# wctrl_led.net
KiCad netlist of a schematic drawn in EAGLE
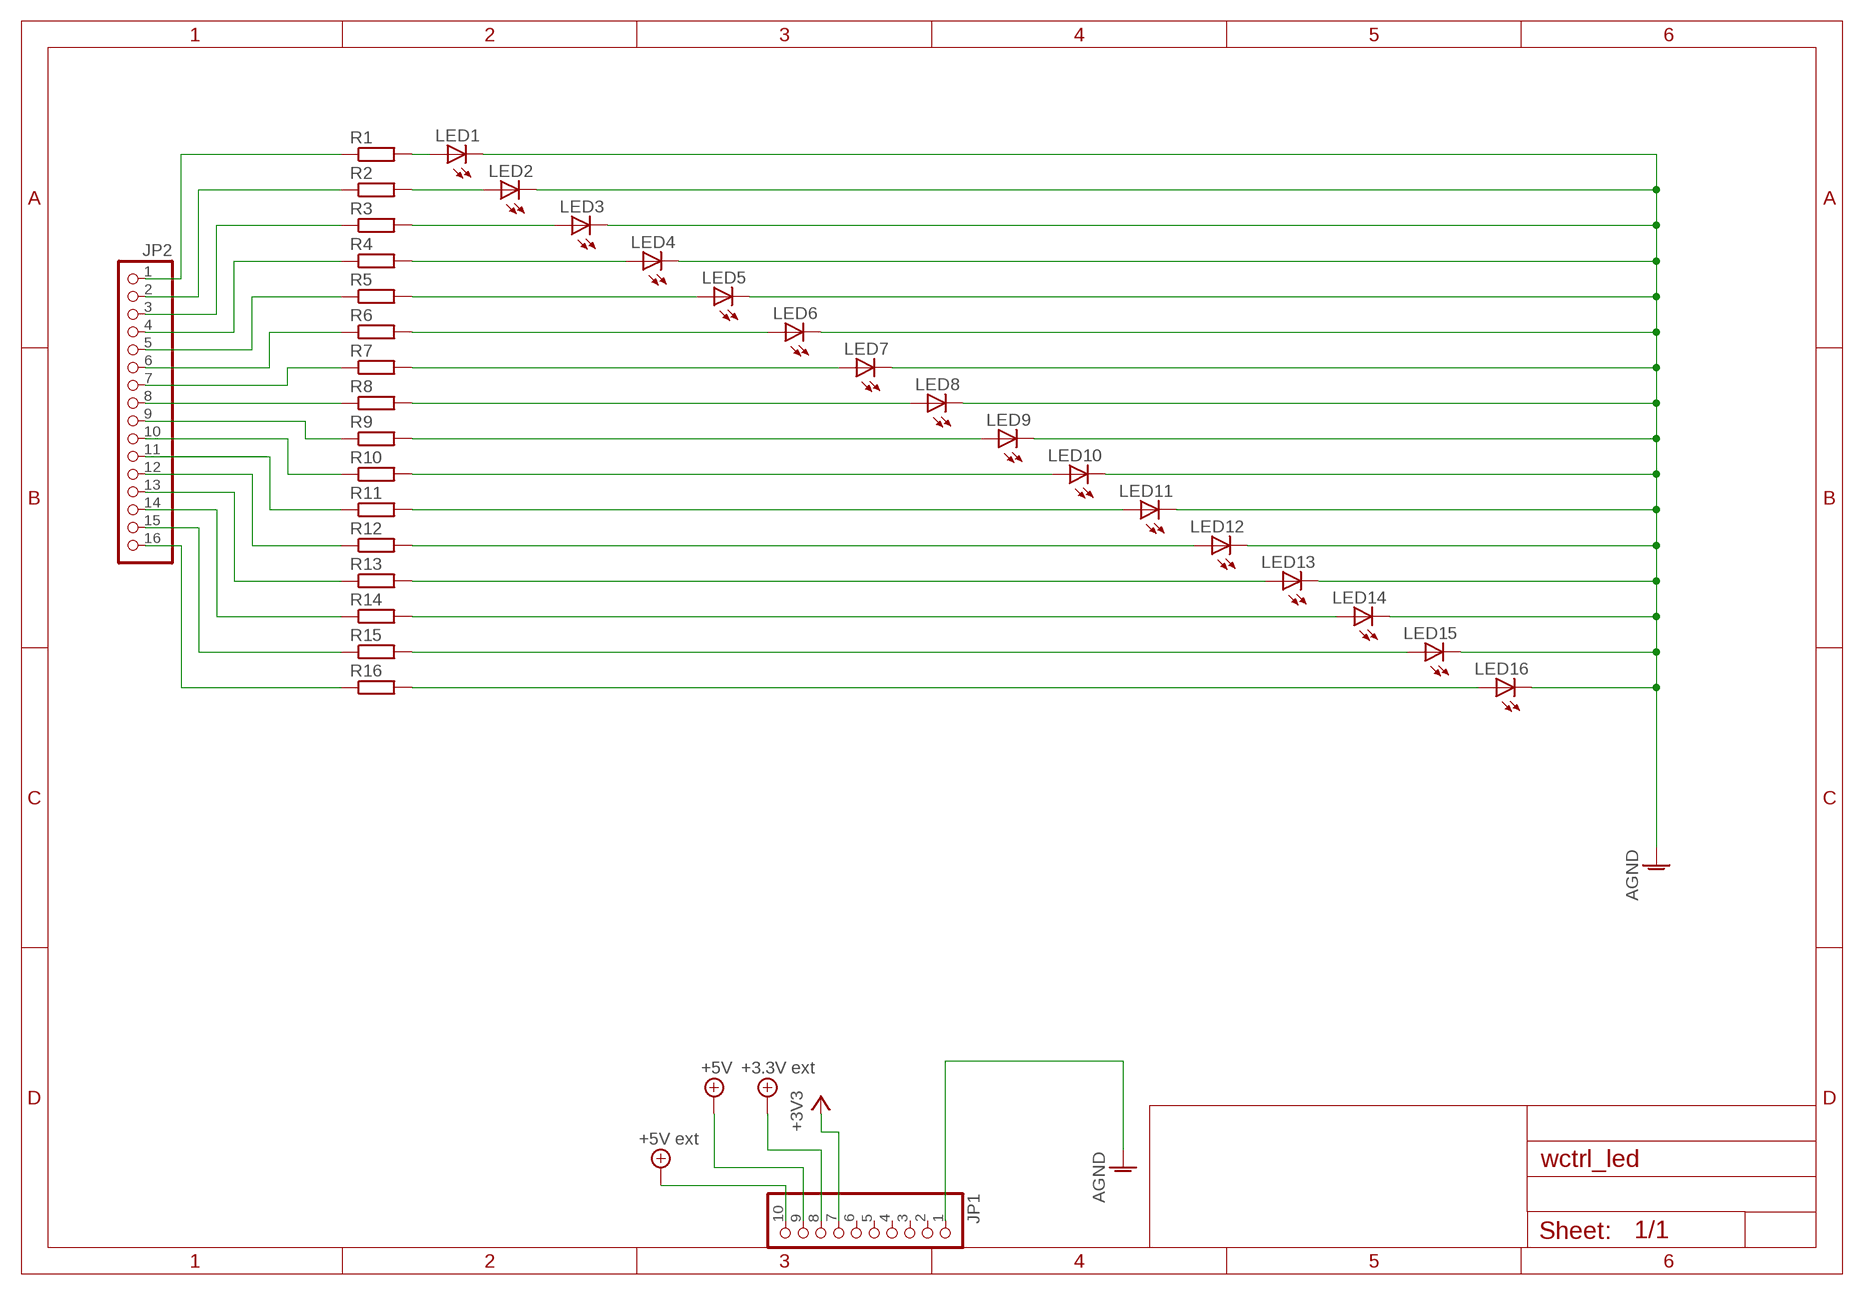
[diagram p0: schematic, sheet 1]

(export (version "E")
  (design (tool "Eeschema 10.0.6"))
  (components
    (comp (ref "JP1")
      (value "PINHD-1X10")
      (footprint "eagle-import:1X10")
      (libsource (lib "eagle-import") (part "PINHD-1X10"))
    )
    (comp (ref "JP2")
      (value "PINHD-1X16")
      (footprint "eagle-import:1X16")
      (libsource (lib "eagle-import") (part "PINHD-1X16"))
    )
    (comp (ref "LED1")
      (value "LED5MM")
      (footprint "eagle-import:LED5MM")
      (libsource (lib "eagle-import") (part "LED5MM"))
    )
    (comp (ref "LED2")
      (value "LED5MM")
      (footprint "eagle-import:LED5MM")
      (libsource (lib "eagle-import") (part "LED5MM"))
    )
    (comp (ref "LED3")
      (value "LED5MM")
      (footprint "eagle-import:LED5MM")
      (libsource (lib "eagle-import") (part "LED5MM"))
    )
    (comp (ref "LED4")
      (value "LED5MM")
      (footprint "eagle-import:LED5MM")
      (libsource (lib "eagle-import") (part "LED5MM"))
    )
    (comp (ref "LED5")
      (value "LED5MM")
      (footprint "eagle-import:LED5MM")
      (libsource (lib "eagle-import") (part "LED5MM"))
    )
    (comp (ref "LED6")
      (value "LED5MM")
      (footprint "eagle-import:LED5MM")
      (libsource (lib "eagle-import") (part "LED5MM"))
    )
    (comp (ref "LED7")
      (value "LED5MM")
      (footprint "eagle-import:LED5MM")
      (libsource (lib "eagle-import") (part "LED5MM"))
    )
    (comp (ref "LED8")
      (value "LED5MM")
      (footprint "eagle-import:LED5MM")
      (libsource (lib "eagle-import") (part "LED5MM"))
    )
    (comp (ref "LED9")
      (value "LED5MM")
      (footprint "eagle-import:LED5MM")
      (libsource (lib "eagle-import") (part "LED5MM"))
    )
    (comp (ref "LED10")
      (value "LED5MM")
      (footprint "eagle-import:LED5MM")
      (libsource (lib "eagle-import") (part "LED5MM"))
    )
    (comp (ref "LED11")
      (value "LED5MM")
      (footprint "eagle-import:LED5MM")
      (libsource (lib "eagle-import") (part "LED5MM"))
    )
    (comp (ref "LED12")
      (value "LED5MM")
      (footprint "eagle-import:LED5MM")
      (libsource (lib "eagle-import") (part "LED5MM"))
    )
    (comp (ref "LED13")
      (value "LED5MM")
      (footprint "eagle-import:LED5MM")
      (libsource (lib "eagle-import") (part "LED5MM"))
    )
    (comp (ref "LED14")
      (value "LED5MM")
      (footprint "eagle-import:LED5MM")
      (libsource (lib "eagle-import") (part "LED5MM"))
    )
    (comp (ref "LED15")
      (value "LED5MM")
      (footprint "eagle-import:LED5MM")
      (libsource (lib "eagle-import") (part "LED5MM"))
    )
    (comp (ref "LED16")
      (value "LED5MM")
      (footprint "eagle-import:LED5MM")
      (libsource (lib "eagle-import") (part "LED5MM"))
    )
    (comp (ref "R1")
      (value "R-EU_0207/10")
      (footprint "eagle-import:0207_10")
      (libsource (lib "eagle-import") (part "R-EU_0207/10"))
    )
    (comp (ref "R2")
      (value "R-EU_0207/10")
      (footprint "eagle-import:0207_10")
      (libsource (lib "eagle-import") (part "R-EU_0207/10"))
    )
    (comp (ref "R3")
      (value "R-EU_0207/10")
      (footprint "eagle-import:0207_10")
      (libsource (lib "eagle-import") (part "R-EU_0207/10"))
    )
    (comp (ref "R4")
      (value "R-EU_0207/10")
      (footprint "eagle-import:0207_10")
      (libsource (lib "eagle-import") (part "R-EU_0207/10"))
    )
    (comp (ref "R5")
      (value "R-EU_0207/10")
      (footprint "eagle-import:0207_10")
      (libsource (lib "eagle-import") (part "R-EU_0207/10"))
    )
    (comp (ref "R6")
      (value "R-EU_0207/10")
      (footprint "eagle-import:0207_10")
      (libsource (lib "eagle-import") (part "R-EU_0207/10"))
    )
    (comp (ref "R7")
      (value "R-EU_0207/10")
      (footprint "eagle-import:0207_10")
      (libsource (lib "eagle-import") (part "R-EU_0207/10"))
    )
    (comp (ref "R8")
      (value "R-EU_0207/10")
      (footprint "eagle-import:0207_10")
      (libsource (lib "eagle-import") (part "R-EU_0207/10"))
    )
    (comp (ref "R9")
      (value "R-EU_0207/10")
      (footprint "eagle-import:0207_10")
      (libsource (lib "eagle-import") (part "R-EU_0207/10"))
    )
    (comp (ref "R10")
      (value "R-EU_0207/10")
      (footprint "eagle-import:0207_10")
      (libsource (lib "eagle-import") (part "R-EU_0207/10"))
    )
    (comp (ref "R11")
      (value "R-EU_0207/10")
      (footprint "eagle-import:0207_10")
      (libsource (lib "eagle-import") (part "R-EU_0207/10"))
    )
    (comp (ref "R12")
      (value "R-EU_0207/10")
      (footprint "eagle-import:0207_10")
      (libsource (lib "eagle-import") (part "R-EU_0207/10"))
    )
    (comp (ref "R13")
      (value "R-EU_0207/10")
      (footprint "eagle-import:0207_10")
      (libsource (lib "eagle-import") (part "R-EU_0207/10"))
    )
    (comp (ref "R14")
      (value "R-EU_0207/10")
      (footprint "eagle-import:0207_10")
      (libsource (lib "eagle-import") (part "R-EU_0207/10"))
    )
    (comp (ref "R15")
      (value "R-EU_0207/10")
      (footprint "eagle-import:0207_10")
      (libsource (lib "eagle-import") (part "R-EU_0207/10"))
    )
    (comp (ref "R16")
      (value "R-EU_0207/10")
      (footprint "eagle-import:0207_10")
      (libsource (lib "eagle-import") (part "R-EU_0207/10"))
    )
  )
  (nets
    (net (code "1") (name "+3.3V ext") (class "Default")
      (node (ref "JP1") (pin "8") (pinfunction "8_8") (pintype "passive"))
    )
    (net (code "2") (name "+3V3") (class "Default")
      (node (ref "JP1") (pin "7") (pinfunction "7_7") (pintype "passive"))
    )
    (net (code "3") (name "+5V") (class "Default")
      (node (ref "JP1") (pin "9") (pinfunction "9_9") (pintype "passive"))
    )
    (net (code "4") (name "+5V ext") (class "Default")
      (node (ref "JP1") (pin "10") (pinfunction "10_10") (pintype "passive"))
    )
    (net (code "5") (name "AGND") (class "Default")
      (node (ref "JP1") (pin "1") (pinfunction "1_1") (pintype "passive"))
      (node (ref "LED1") (pin "K") (pinfunction "C_K") (pintype "passive"))
      (node (ref "LED10") (pin "K") (pinfunction "C_K") (pintype "passive"))
      (node (ref "LED11") (pin "K") (pinfunction "C_K") (pintype "passive"))
      (node (ref "LED12") (pin "K") (pinfunction "C_K") (pintype "passive"))
      (node (ref "LED13") (pin "K") (pinfunction "C_K") (pintype "passive"))
      (node (ref "LED14") (pin "K") (pinfunction "C_K") (pintype "passive"))
      (node (ref "LED15") (pin "K") (pinfunction "C_K") (pintype "passive"))
      (node (ref "LED16") (pin "K") (pinfunction "C_K") (pintype "passive"))
      (node (ref "LED2") (pin "K") (pinfunction "C_K") (pintype "passive"))
      (node (ref "LED3") (pin "K") (pinfunction "C_K") (pintype "passive"))
      (node (ref "LED4") (pin "K") (pinfunction "C_K") (pintype "passive"))
      (node (ref "LED5") (pin "K") (pinfunction "C_K") (pintype "passive"))
      (node (ref "LED6") (pin "K") (pinfunction "C_K") (pintype "passive"))
      (node (ref "LED7") (pin "K") (pinfunction "C_K") (pintype "passive"))
      (node (ref "LED8") (pin "K") (pinfunction "C_K") (pintype "passive"))
      (node (ref "LED9") (pin "K") (pinfunction "C_K") (pintype "passive"))
    )
    (net (code "6") (name "Net-(JP2-Pad1)") (class "Default")
      (node (ref "JP2") (pin "1") (pinfunction "1_1") (pintype "passive"))
      (node (ref "R1") (pin "1") (pinfunction "1_1") (pintype "passive"))
    )
    (net (code "7") (name "Net-(JP2-Pad2)") (class "Default")
      (node (ref "JP2") (pin "2") (pinfunction "2_2") (pintype "passive"))
      (node (ref "R2") (pin "1") (pinfunction "1_1") (pintype "passive"))
    )
    (net (code "8") (name "Net-(JP2-Pad3)") (class "Default")
      (node (ref "JP2") (pin "3") (pinfunction "3_3") (pintype "passive"))
      (node (ref "R3") (pin "1") (pinfunction "1_1") (pintype "passive"))
    )
    (net (code "9") (name "Net-(JP2-Pad4)") (class "Default")
      (node (ref "JP2") (pin "4") (pinfunction "4_4") (pintype "passive"))
      (node (ref "R4") (pin "1") (pinfunction "1_1") (pintype "passive"))
    )
    (net (code "10") (name "Net-(JP2-Pad5)") (class "Default")
      (node (ref "JP2") (pin "5") (pinfunction "5_5") (pintype "passive"))
      (node (ref "R5") (pin "1") (pinfunction "1_1") (pintype "passive"))
    )
    (net (code "11") (name "Net-(JP2-Pad6)") (class "Default")
      (node (ref "JP2") (pin "6") (pinfunction "6_6") (pintype "passive"))
      (node (ref "R6") (pin "1") (pinfunction "1_1") (pintype "passive"))
    )
    (net (code "12") (name "Net-(JP2-Pad7)") (class "Default")
      (node (ref "JP2") (pin "7") (pinfunction "7_7") (pintype "passive"))
      (node (ref "R7") (pin "1") (pinfunction "1_1") (pintype "passive"))
    )
    (net (code "13") (name "Net-(JP2-Pad8)") (class "Default")
      (node (ref "JP2") (pin "8") (pinfunction "8_8") (pintype "passive"))
      (node (ref "R8") (pin "1") (pinfunction "1_1") (pintype "passive"))
    )
    (net (code "14") (name "Net-(JP2-Pad9)") (class "Default")
      (node (ref "JP2") (pin "9") (pinfunction "9_9") (pintype "passive"))
      (node (ref "R9") (pin "1") (pinfunction "1_1") (pintype "passive"))
    )
    (net (code "15") (name "Net-(JP2-Pad10)") (class "Default")
      (node (ref "JP2") (pin "10") (pinfunction "10_10") (pintype "passive"))
      (node (ref "R10") (pin "1") (pinfunction "1_1") (pintype "passive"))
    )
    (net (code "16") (name "Net-(JP2-Pad11)") (class "Default")
      (node (ref "JP2") (pin "11") (pinfunction "11_11") (pintype "passive"))
      (node (ref "R11") (pin "1") (pinfunction "1_1") (pintype "passive"))
    )
    (net (code "17") (name "Net-(JP2-Pad12)") (class "Default")
      (node (ref "JP2") (pin "12") (pinfunction "12_12") (pintype "passive"))
      (node (ref "R12") (pin "1") (pinfunction "1_1") (pintype "passive"))
    )
    (net (code "18") (name "Net-(JP2-Pad13)") (class "Default")
      (node (ref "JP2") (pin "13") (pinfunction "13_13") (pintype "passive"))
      (node (ref "R13") (pin "1") (pinfunction "1_1") (pintype "passive"))
    )
    (net (code "19") (name "Net-(JP2-Pad14)") (class "Default")
      (node (ref "JP2") (pin "14") (pinfunction "14_14") (pintype "passive"))
      (node (ref "R14") (pin "1") (pinfunction "1_1") (pintype "passive"))
    )
    (net (code "20") (name "Net-(JP2-Pad15)") (class "Default")
      (node (ref "JP2") (pin "15") (pinfunction "15_15") (pintype "passive"))
      (node (ref "R15") (pin "1") (pinfunction "1_1") (pintype "passive"))
    )
    (net (code "21") (name "Net-(JP2-Pad16)") (class "Default")
      (node (ref "JP2") (pin "16") (pinfunction "16_16") (pintype "passive"))
      (node (ref "R16") (pin "1") (pinfunction "1_1") (pintype "passive"))
    )
    (net (code "22") (name "Net-(LED1-PadA)") (class "Default")
      (node (ref "LED1") (pin "A") (pinfunction "A_A") (pintype "passive"))
      (node (ref "R1") (pin "2") (pinfunction "2_2") (pintype "passive"))
    )
    (net (code "23") (name "Net-(LED2-PadA)") (class "Default")
      (node (ref "LED2") (pin "A") (pinfunction "A_A") (pintype "passive"))
      (node (ref "R2") (pin "2") (pinfunction "2_2") (pintype "passive"))
    )
    (net (code "24") (name "Net-(LED3-PadA)") (class "Default")
      (node (ref "LED3") (pin "A") (pinfunction "A_A") (pintype "passive"))
      (node (ref "R3") (pin "2") (pinfunction "2_2") (pintype "passive"))
    )
    (net (code "25") (name "Net-(LED4-PadA)") (class "Default")
      (node (ref "LED4") (pin "A") (pinfunction "A_A") (pintype "passive"))
      (node (ref "R4") (pin "2") (pinfunction "2_2") (pintype "passive"))
    )
    (net (code "26") (name "Net-(LED5-PadA)") (class "Default")
      (node (ref "LED5") (pin "A") (pinfunction "A_A") (pintype "passive"))
      (node (ref "R5") (pin "2") (pinfunction "2_2") (pintype "passive"))
    )
    (net (code "27") (name "Net-(LED6-PadA)") (class "Default")
      (node (ref "LED6") (pin "A") (pinfunction "A_A") (pintype "passive"))
      (node (ref "R6") (pin "2") (pinfunction "2_2") (pintype "passive"))
    )
    (net (code "28") (name "Net-(LED7-PadA)") (class "Default")
      (node (ref "LED7") (pin "A") (pinfunction "A_A") (pintype "passive"))
      (node (ref "R7") (pin "2") (pinfunction "2_2") (pintype "passive"))
    )
    (net (code "29") (name "Net-(LED8-PadA)") (class "Default")
      (node (ref "LED8") (pin "A") (pinfunction "A_A") (pintype "passive"))
      (node (ref "R8") (pin "2") (pinfunction "2_2") (pintype "passive"))
    )
    (net (code "30") (name "Net-(LED9-PadA)") (class "Default")
      (node (ref "LED9") (pin "A") (pinfunction "A_A") (pintype "passive"))
      (node (ref "R9") (pin "2") (pinfunction "2_2") (pintype "passive"))
    )
    (net (code "31") (name "Net-(LED10-PadA)") (class "Default")
      (node (ref "LED10") (pin "A") (pinfunction "A_A") (pintype "passive"))
      (node (ref "R10") (pin "2") (pinfunction "2_2") (pintype "passive"))
    )
    (net (code "32") (name "Net-(LED11-PadA)") (class "Default")
      (node (ref "LED11") (pin "A") (pinfunction "A_A") (pintype "passive"))
      (node (ref "R11") (pin "2") (pinfunction "2_2") (pintype "passive"))
    )
    (net (code "33") (name "Net-(LED12-PadA)") (class "Default")
      (node (ref "LED12") (pin "A") (pinfunction "A_A") (pintype "passive"))
      (node (ref "R12") (pin "2") (pinfunction "2_2") (pintype "passive"))
    )
    (net (code "34") (name "Net-(LED13-PadA)") (class "Default")
      (node (ref "LED13") (pin "A") (pinfunction "A_A") (pintype "passive"))
      (node (ref "R13") (pin "2") (pinfunction "2_2") (pintype "passive"))
    )
    (net (code "35") (name "Net-(LED14-PadA)") (class "Default")
      (node (ref "LED14") (pin "A") (pinfunction "A_A") (pintype "passive"))
      (node (ref "R14") (pin "2") (pinfunction "2_2") (pintype "passive"))
    )
    (net (code "36") (name "Net-(LED15-PadA)") (class "Default")
      (node (ref "LED15") (pin "A") (pinfunction "A_A") (pintype "passive"))
      (node (ref "R15") (pin "2") (pinfunction "2_2") (pintype "passive"))
    )
    (net (code "37") (name "Net-(LED16-PadA)") (class "Default")
      (node (ref "LED16") (pin "A") (pinfunction "A_A") (pintype "passive"))
      (node (ref "R16") (pin "2") (pinfunction "2_2") (pintype "passive"))
    )
    (net (code "38") (name "unconnected-(JP1-Pad2)") (class "Default")
      (node (ref "JP1") (pin "2") (pinfunction "2_2") (pintype "passive"))
    )
    (net (code "39") (name "unconnected-(JP1-Pad3)") (class "Default")
      (node (ref "JP1") (pin "3") (pinfunction "3_3") (pintype "passive"))
    )
    (net (code "40") (name "unconnected-(JP1-Pad4)") (class "Default")
      (node (ref "JP1") (pin "4") (pinfunction "4_4") (pintype "passive"))
    )
    (net (code "41") (name "unconnected-(JP1-Pad5)") (class "Default")
      (node (ref "JP1") (pin "5") (pinfunction "5_5") (pintype "passive"))
    )
    (net (code "42") (name "unconnected-(JP1-Pad6)") (class "Default")
      (node (ref "JP1") (pin "6") (pinfunction "6_6") (pintype "passive"))
    )
  )
)
